# Motor_h_bruecke.net
KiCad netlist of a schematic drawn in EAGLE
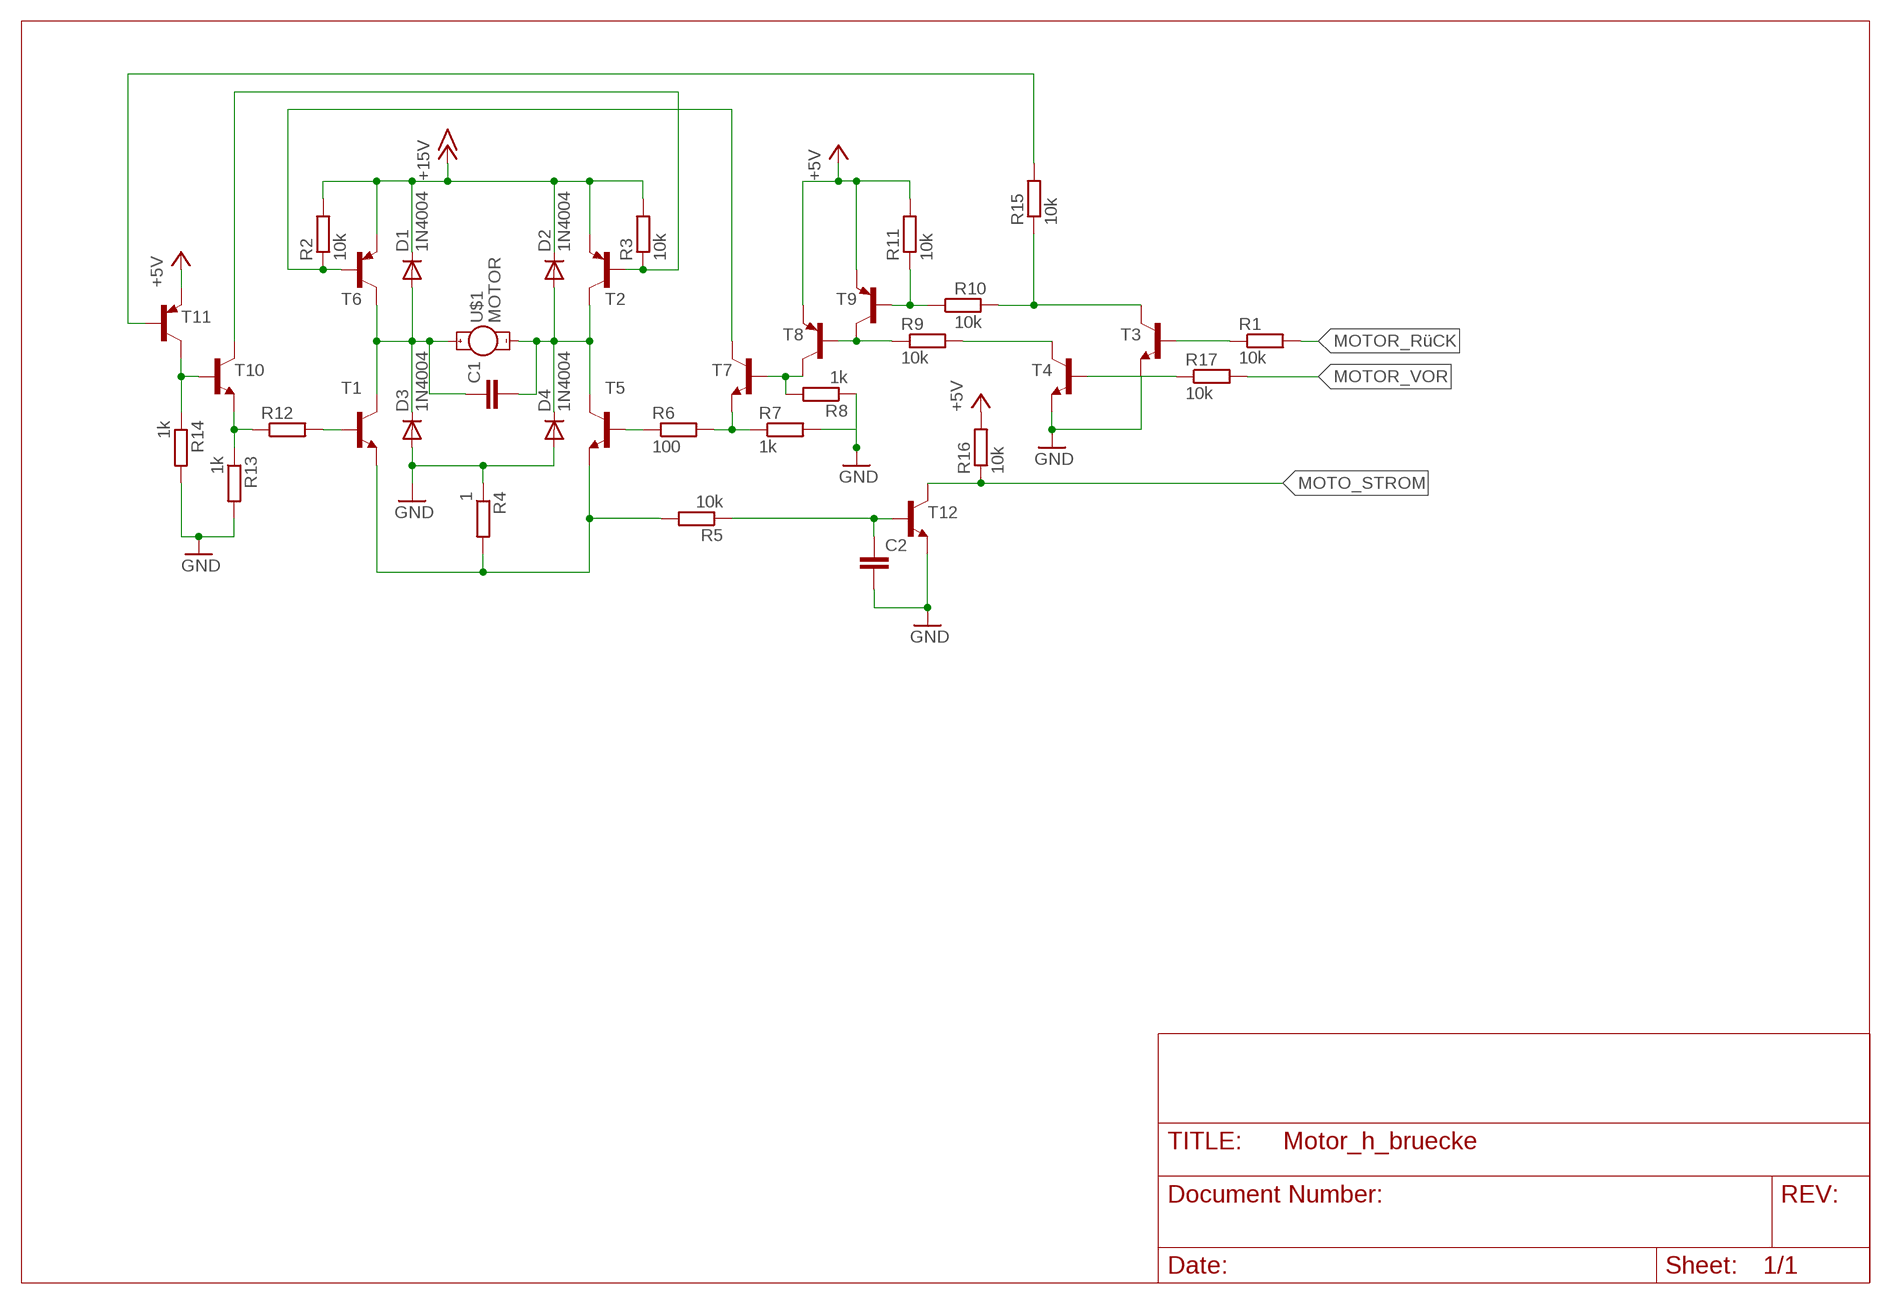
[diagram p0: schematic, sheet 1]

(export (version "E")
  (design (tool "Eeschema 10.0.6"))
  (components
    (comp (ref "C1")
      (value "C-EUC0805")
      (footprint "eagle-import:C0805")
      (libsource (lib "eagle-import") (part "C-EUC0805"))
    )
    (comp (ref "C2")
      (value "C-EUC0805")
      (footprint "eagle-import:C0805")
      (libsource (lib "eagle-import") (part "C-EUC0805"))
    )
    (comp (ref "D1")
      (value "1N4004")
      (footprint "eagle-import:DO41-10")
      (libsource (lib "eagle-import") (part "1N4004"))
    )
    (comp (ref "D2")
      (value "1N4004")
      (footprint "eagle-import:DO41-10")
      (libsource (lib "eagle-import") (part "1N4004"))
    )
    (comp (ref "D3")
      (value "1N4004")
      (footprint "eagle-import:DO41-10")
      (libsource (lib "eagle-import") (part "1N4004"))
    )
    (comp (ref "D4")
      (value "1N4004")
      (footprint "eagle-import:DO41-10")
      (libsource (lib "eagle-import") (part "1N4004"))
    )
    (comp (ref "R1")
      (value "10k")
      (footprint "eagle-import:R0805")
      (libsource (lib "eagle-import") (part "R-EU_R0805"))
    )
    (comp (ref "R2")
      (value "10k")
      (footprint "eagle-import:R0805")
      (libsource (lib "eagle-import") (part "R-EU_R0805"))
    )
    (comp (ref "R3")
      (value "10k")
      (footprint "eagle-import:R0805")
      (libsource (lib "eagle-import") (part "R-EU_R0805"))
    )
    (comp (ref "R4")
      (value "1")
      (footprint "eagle-import:R0805")
      (libsource (lib "eagle-import") (part "R-EU_R0805"))
    )
    (comp (ref "R5")
      (value "10k")
      (footprint "eagle-import:R0805")
      (libsource (lib "eagle-import") (part "R-EU_R0805"))
    )
    (comp (ref "R6")
      (value "100")
      (footprint "eagle-import:R0805")
      (libsource (lib "eagle-import") (part "R-EU_R0805"))
    )
    (comp (ref "R7")
      (value "1k")
      (footprint "eagle-import:R0805")
      (libsource (lib "eagle-import") (part "R-EU_R0805"))
    )
    (comp (ref "R8")
      (value "1k")
      (footprint "eagle-import:R0805")
      (libsource (lib "eagle-import") (part "R-EU_R0805"))
    )
    (comp (ref "R9")
      (value "10k")
      (footprint "eagle-import:R0805")
      (libsource (lib "eagle-import") (part "R-EU_R0805"))
    )
    (comp (ref "R10")
      (value "10k")
      (footprint "eagle-import:R0805")
      (libsource (lib "eagle-import") (part "R-EU_R0805"))
    )
    (comp (ref "R11")
      (value "10k")
      (footprint "eagle-import:R0805")
      (libsource (lib "eagle-import") (part "R-EU_R0805"))
    )
    (comp (ref "R12")
      (value "R-EU_R0805")
      (footprint "eagle-import:R0805")
      (libsource (lib "eagle-import") (part "R-EU_R0805"))
    )
    (comp (ref "R13")
      (value "1k")
      (footprint "eagle-import:R0805")
      (libsource (lib "eagle-import") (part "R-EU_R0805"))
    )
    (comp (ref "R14")
      (value "1k")
      (footprint "eagle-import:R0805")
      (libsource (lib "eagle-import") (part "R-EU_R0805"))
    )
    (comp (ref "R15")
      (value "10k")
      (footprint "eagle-import:R0805")
      (libsource (lib "eagle-import") (part "R-EU_R0805"))
    )
    (comp (ref "R16")
      (value "10k")
      (footprint "eagle-import:R0805")
      (libsource (lib "eagle-import") (part "R-EU_R0805"))
    )
    (comp (ref "R17")
      (value "10k")
      (footprint "eagle-import:R0805")
      (libsource (lib "eagle-import") (part "R-EU_R0805"))
    )
    (comp (ref "T1")
      (value "-NPN-TO225AA")
      (footprint "eagle-import:TO225AA")
      (libsource (lib "eagle-import") (part "-NPN-TO225AA"))
    )
    (comp (ref "T2")
      (value "-PNP-TO225AA")
      (footprint "eagle-import:TO225AA")
      (libsource (lib "eagle-import") (part "-PNP-TO225AA"))
    )
    (comp (ref "T3")
      (value "BC337-40-NPN-TO92-CBE")
      (footprint "eagle-import:TO92-CBE")
      (libsource (lib "eagle-import") (part "-NPN-TO92-CBEBC337-40"))
    )
    (comp (ref "T4")
      (value "BC337-40-NPN-TO92-CBE")
      (footprint "eagle-import:TO92-CBE")
      (libsource (lib "eagle-import") (part "-NPN-TO92-CBEBC337-40"))
    )
    (comp (ref "T5")
      (value "-NPN-TO225AA")
      (footprint "eagle-import:TO225AA")
      (libsource (lib "eagle-import") (part "-NPN-TO225AA"))
    )
    (comp (ref "T6")
      (value "-PNP-TO225AA")
      (footprint "eagle-import:TO225AA")
      (libsource (lib "eagle-import") (part "-PNP-TO225AA"))
    )
    (comp (ref "T7")
      (value "BC808-NPN-SOT23-BEC")
      (footprint "eagle-import:SOT23-BEC")
      (libsource (lib "eagle-import") (part "-NPN-SOT23-BECBC808"))
    )
    (comp (ref "T8")
      (value "BC807-16-PNP-SOT23-BEC")
      (footprint "eagle-import:SOT23-BEC")
      (libsource (lib "eagle-import") (part "-PNP-SOT23-BECBC807-16"))
    )
    (comp (ref "T9")
      (value "BC807-16-PNP-SOT23-BEC")
      (footprint "eagle-import:SOT23-BEC")
      (libsource (lib "eagle-import") (part "-PNP-SOT23-BECBC807-16"))
    )
    (comp (ref "T10")
      (value "BC808-NPN-SOT23-BEC")
      (footprint "eagle-import:SOT23-BEC")
      (libsource (lib "eagle-import") (part "-NPN-SOT23-BECBC808"))
    )
    (comp (ref "T11")
      (value "BC807-16-PNP-SOT23-BEC")
      (footprint "eagle-import:SOT23-BEC")
      (libsource (lib "eagle-import") (part "-PNP-SOT23-BECBC807-16"))
    )
    (comp (ref "T12")
      (value "BC808-NPN-SOT23-BEC")
      (footprint "eagle-import:SOT23-BEC")
      (libsource (lib "eagle-import") (part "-NPN-SOT23-BECBC808"))
    )
    (comp (ref "U$1")
      (value "MOTOR")
      (footprint "eagle-import:VIBE-MOTOR-10MM")
      (libsource (lib "eagle-import") (part "MOTOR10MM"))
    )
  )
  (nets
    (net (code "1") (name "+5V") (class "Default")
      (node (ref "R11") (pin "2") (pinfunction "2_2") (pintype "passive"))
      (node (ref "R16") (pin "2") (pinfunction "2_2") (pintype "passive"))
      (node (ref "T11") (pin "E") (pinfunction "E_E") (pintype "passive"))
      (node (ref "T8") (pin "E") (pinfunction "E_E") (pintype "passive"))
      (node (ref "T9") (pin "E") (pinfunction "E_E") (pintype "passive"))
    )
    (net (code "2") (name "+15V") (class "Default")
      (node (ref "D1") (pin "C") (pinfunction "C_C") (pintype "passive"))
      (node (ref "D2") (pin "C") (pinfunction "C_C") (pintype "passive"))
      (node (ref "R2") (pin "2") (pinfunction "2_2") (pintype "passive"))
      (node (ref "R3") (pin "2") (pinfunction "2_2") (pintype "passive"))
      (node (ref "T2") (pin "3") (pinfunction "E_3") (pintype "passive"))
      (node (ref "T6") (pin "3") (pinfunction "E_3") (pintype "passive"))
    )
    (net (code "3") (name "GND") (class "Default")
      (node (ref "C2") (pin "2") (pinfunction "2_2") (pintype "passive"))
      (node (ref "D3") (pin "A") (pinfunction "A_A") (pintype "passive"))
      (node (ref "D4") (pin "A") (pinfunction "A_A") (pintype "passive"))
      (node (ref "R13") (pin "2") (pinfunction "2_2") (pintype "passive"))
      (node (ref "R14") (pin "2") (pinfunction "2_2") (pintype "passive"))
      (node (ref "R4") (pin "1") (pinfunction "1_1") (pintype "passive"))
      (node (ref "R7") (pin "2") (pinfunction "2_2") (pintype "passive"))
      (node (ref "R8") (pin "1") (pinfunction "1_1") (pintype "passive"))
      (node (ref "T12") (pin "E") (pinfunction "E_E") (pintype "passive"))
      (node (ref "T3") (pin "E") (pinfunction "E_E") (pintype "passive"))
      (node (ref "T4") (pin "E") (pinfunction "E_E") (pintype "passive"))
    )
    (net (code "4") (name "MOTOR_RüCK") (class "Default")
      (node (ref "R1") (pin "2") (pinfunction "2_2") (pintype "passive"))
    )
    (net (code "5") (name "MOTOR_VOR") (class "Default")
      (node (ref "R17") (pin "2") (pinfunction "2_2") (pintype "passive"))
    )
    (net (code "6") (name "MOTO_STROM") (class "Default")
      (node (ref "R16") (pin "1") (pinfunction "1_1") (pintype "passive"))
      (node (ref "T12") (pin "C") (pinfunction "C_C") (pintype "passive"))
    )
    (net (code "7") (name "Net-(C2-Pad1)") (class "Default")
      (node (ref "C2") (pin "1") (pinfunction "1_1") (pintype "passive"))
      (node (ref "R5") (pin "1") (pinfunction "1_1") (pintype "passive"))
      (node (ref "T12") (pin "B") (pinfunction "B_B") (pintype "passive"))
    )
    (net (code "8") (name "Net-(R1-Pad1)") (class "Default")
      (node (ref "R1") (pin "1") (pinfunction "1_1") (pintype "passive"))
      (node (ref "T3") (pin "B") (pinfunction "B_B") (pintype "passive"))
    )
    (net (code "9") (name "Net-(R6-Pad2)") (class "Default")
      (node (ref "R6") (pin "2") (pinfunction "2_2") (pintype "passive"))
      (node (ref "R7") (pin "1") (pinfunction "1_1") (pintype "passive"))
      (node (ref "T7") (pin "E") (pinfunction "E_E") (pintype "passive"))
    )
    (net (code "10") (name "Net-(R8-Pad2)") (class "Default")
      (node (ref "R8") (pin "2") (pinfunction "2_2") (pintype "passive"))
      (node (ref "T7") (pin "B") (pinfunction "B_B") (pintype "passive"))
      (node (ref "T8") (pin "C") (pinfunction "C_C") (pintype "passive"))
    )
    (net (code "11") (name "Net-(R9-Pad1)") (class "Default")
      (node (ref "R9") (pin "1") (pinfunction "1_1") (pintype "passive"))
      (node (ref "T8") (pin "B") (pinfunction "B_B") (pintype "passive"))
      (node (ref "T9") (pin "C") (pinfunction "C_C") (pintype "passive"))
    )
    (net (code "12") (name "Net-(R9-Pad2)") (class "Default")
      (node (ref "R9") (pin "2") (pinfunction "2_2") (pintype "passive"))
      (node (ref "T4") (pin "C") (pinfunction "C_C") (pintype "passive"))
    )
    (net (code "13") (name "Net-(R10-Pad1)") (class "Default")
      (node (ref "R10") (pin "1") (pinfunction "1_1") (pintype "passive"))
      (node (ref "R11") (pin "1") (pinfunction "1_1") (pintype "passive"))
      (node (ref "T9") (pin "B") (pinfunction "B_B") (pintype "passive"))
    )
    (net (code "14") (name "Net-(R10-Pad2)") (class "Default")
      (node (ref "R10") (pin "2") (pinfunction "2_2") (pintype "passive"))
      (node (ref "R15") (pin "1") (pinfunction "1_1") (pintype "passive"))
      (node (ref "T3") (pin "C") (pinfunction "C_C") (pintype "passive"))
    )
    (net (code "15") (name "Net-(R12-Pad1)") (class "Default")
      (node (ref "R12") (pin "1") (pinfunction "1_1") (pintype "passive"))
      (node (ref "R13") (pin "1") (pinfunction "1_1") (pintype "passive"))
      (node (ref "T10") (pin "E") (pinfunction "E_E") (pintype "passive"))
    )
    (net (code "16") (name "Net-(R14-Pad1)") (class "Default")
      (node (ref "R14") (pin "1") (pinfunction "1_1") (pintype "passive"))
      (node (ref "T10") (pin "B") (pinfunction "B_B") (pintype "passive"))
      (node (ref "T11") (pin "C") (pinfunction "C_C") (pintype "passive"))
    )
    (net (code "17") (name "Net-(R15-Pad2)") (class "Default")
      (node (ref "R15") (pin "2") (pinfunction "2_2") (pintype "passive"))
      (node (ref "T11") (pin "B") (pinfunction "B_B") (pintype "passive"))
    )
    (net (code "18") (name "Net-(R17-Pad1)") (class "Default")
      (node (ref "R17") (pin "1") (pinfunction "1_1") (pintype "passive"))
      (node (ref "T4") (pin "B") (pinfunction "B_B") (pintype "passive"))
    )
    (net (code "19") (name "Net-(T1-B)") (class "Default")
      (node (ref "R12") (pin "2") (pinfunction "2_2") (pintype "passive"))
      (node (ref "T1") (pin "1") (pinfunction "B_1") (pintype "passive"))
    )
    (net (code "20") (name "Net-(T1-C)") (class "Default")
      (node (ref "C1") (pin "1") (pinfunction "1_1") (pintype "passive"))
      (node (ref "D1") (pin "A") (pinfunction "A_A") (pintype "passive"))
      (node (ref "D3") (pin "C") (pinfunction "C_C") (pintype "passive"))
      (node (ref "T1") (pin "2") (pinfunction "C_2") (pintype "passive"))
      (node (ref "T6") (pin "2") (pinfunction "C_2") (pintype "passive"))
      (node (ref "U$1") (pin "+") (pinfunction "+_+") (pintype "bidirectional"))
    )
    (net (code "21") (name "Net-(T1-E)") (class "Default")
      (node (ref "R4") (pin "2") (pinfunction "2_2") (pintype "passive"))
      (node (ref "R5") (pin "2") (pinfunction "2_2") (pintype "passive"))
      (node (ref "T1") (pin "3") (pinfunction "E_3") (pintype "passive"))
      (node (ref "T5") (pin "3") (pinfunction "E_3") (pintype "passive"))
    )
    (net (code "22") (name "Net-(T2-B)") (class "Default")
      (node (ref "R3") (pin "1") (pinfunction "1_1") (pintype "passive"))
      (node (ref "T10") (pin "C") (pinfunction "C_C") (pintype "passive"))
      (node (ref "T2") (pin "1") (pinfunction "B_1") (pintype "passive"))
    )
    (net (code "23") (name "Net-(T2-C)") (class "Default")
      (node (ref "C1") (pin "2") (pinfunction "2_2") (pintype "passive"))
      (node (ref "D2") (pin "A") (pinfunction "A_A") (pintype "passive"))
      (node (ref "D4") (pin "C") (pinfunction "C_C") (pintype "passive"))
      (node (ref "T2") (pin "2") (pinfunction "C_2") (pintype "passive"))
      (node (ref "T5") (pin "2") (pinfunction "C_2") (pintype "passive"))
      (node (ref "U$1") (pin "-") (pinfunction "-_-") (pintype "bidirectional"))
    )
    (net (code "24") (name "Net-(T5-B)") (class "Default")
      (node (ref "R6") (pin "1") (pinfunction "1_1") (pintype "passive"))
      (node (ref "T5") (pin "1") (pinfunction "B_1") (pintype "passive"))
    )
    (net (code "25") (name "Net-(T6-B)") (class "Default")
      (node (ref "R2") (pin "1") (pinfunction "1_1") (pintype "passive"))
      (node (ref "T6") (pin "1") (pinfunction "B_1") (pintype "passive"))
      (node (ref "T7") (pin "C") (pinfunction "C_C") (pintype "passive"))
    )
  )
)
